# GameBoard.net
KiCad netlist of a schematic drawn in Altium Designer
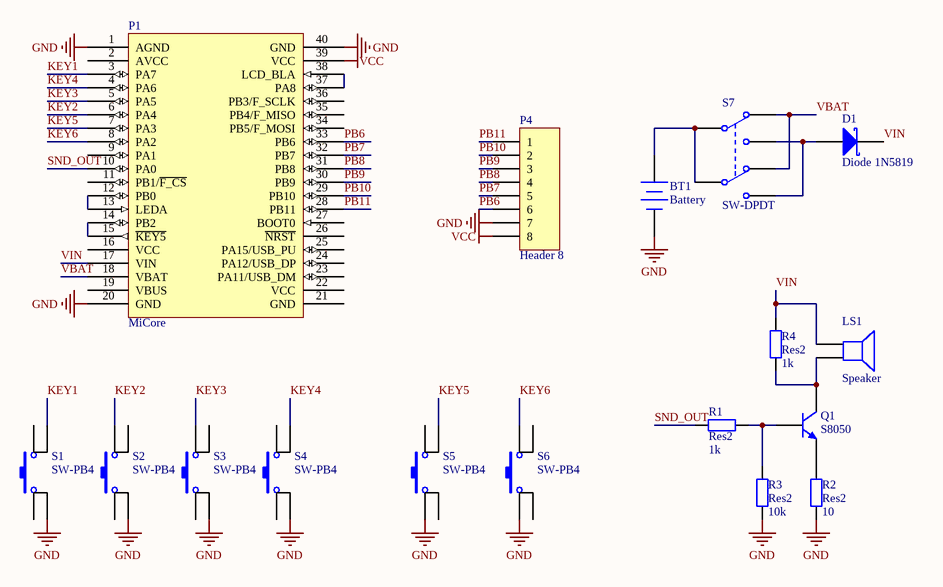
[diagram p0: GameBoard.SchDoc]

(export (version "E")
  (design (tool "Eeschema 10.0.6"))
  (components
    (comp (ref "BT1")
      (value "Battery")
      (footprint "BAT-2")
      (description "Multicell Battery")
      (fields (field (name "PUBLISHER") "Altium Limited"))
      (libsource (lib "Miscellaneous Devices") (part "Battery"))
    )
    (comp (ref "D1")
      (value "Diode 1N5819")
      (footprint "DO-204AL")
      (description "Schottky Rectifier")
      (fields (field (name "PUBLISHER") "Altium Limited"))
      (libsource (lib "Miscellaneous Devices") (part "Diode 11DQ03"))
    )
    (comp (ref "LS1")
      (value "Speaker")
      (footprint "PIN2")
      (description "Loudspeaker")
      (fields (field (name "PUBLISHER") "Altium Limited"))
      (libsource (lib "Miscellaneous Devices") (part "Speaker"))
    )
    (comp (ref "P1") (value "MiCore") (description "MiCore核心板") (libsource (lib "MiCore") (part "MiCore")))
    (comp (ref "P4")
      (value "Header 8")
      (footprint "HDR1X8")
      (description "Header, 8-Pin")
      (fields (field (name "PUBLISHER") "Altium Limited"))
      (libsource (lib "Miscellaneous Connectors") (part "Header 8"))
    )
    (comp (ref "Q1")
      (value "S8050")
      (footprint "TO-92")
      (description "NPN Bipolar Transistor")
      (fields (field (name "PUBLISHER") "Altium Limited"))
      (libsource (lib "Schlib1") (part "NPN"))
    )
    (comp (ref "R1")
      (value "Res2")
      (footprint "AXIAL-0.4")
      (description "Resistor")
      (fields (field (name "ALTIUM_VALUE") "1k") (field (name "PUBLISHER") "Altium Limited"))
      (libsource (lib "") (part "Res2_1"))
    )
    (comp (ref "R2")
      (value "Res2")
      (footprint "AXIAL-0.4")
      (description "Resistor")
      (fields (field (name "ALTIUM_VALUE") "10") (field (name "PUBLISHER") "Altium Limited"))
      (libsource (lib "Miscellaneous Devices") (part "Res2"))
    )
    (comp (ref "R3")
      (value "Res2")
      (footprint "AXIAL-0.4")
      (description "Resistor")
      (fields (field (name "ALTIUM_VALUE") "10k") (field (name "PUBLISHER") "Altium Limited"))
      (libsource (lib "Miscellaneous Devices") (part "Res2"))
    )
    (comp (ref "R4")
      (value "Res2")
      (footprint "AXIAL-0.4")
      (description "Resistor")
      (fields (field (name "ALTIUM_VALUE") "1k") (field (name "PUBLISHER") "Altium Limited"))
      (libsource (lib "Miscellaneous Devices") (part "Res2"))
    )
    (comp (ref "S1")
      (value "SW-PB4")
      (footprint "SW-PB-4P")
      (description "普通4脚按键")
      (libsource (lib "Schlib1") (part "SW-PB4"))
    )
    (comp (ref "S2")
      (value "SW-PB4")
      (footprint "SW-PB-4P")
      (description "普通4脚按键")
      (libsource (lib "Schlib1") (part "SW-PB4"))
    )
    (comp (ref "S3")
      (value "SW-PB4")
      (footprint "SW-PB-4P")
      (description "普通4脚按键")
      (libsource (lib "Schlib1") (part "SW-PB4"))
    )
    (comp (ref "S4")
      (value "SW-PB4")
      (footprint "SW-PB-4P")
      (description "普通4脚按键")
      (libsource (lib "Schlib1") (part "SW-PB4"))
    )
    (comp (ref "S5")
      (value "SW-PB4")
      (footprint "SW-PB-4P")
      (description "普通4脚按键")
      (libsource (lib "Schlib1") (part "SW-PB4"))
    )
    (comp (ref "S6")
      (value "SW-PB4")
      (footprint "SW-PB-4P")
      (description "普通4脚按键")
      (libsource (lib "Schlib1") (part "SW-PB4"))
    )
    (comp (ref "S7")
      (value "SW-DPDT")
      (footprint "DPDT-6P")
      (description "双刀双掷开关")
      (fields (field (name "PUBLISHER") "Altium Limited"))
      (libsource (lib "Schlib1") (part "SW-DPDT"))
    )
  )
  (nets
    (net (code "1") (name "/KEY1") (class "Default")
      (node (ref "P1") (pin "3") (pinfunction "PA7_3") (pintype "bidirectional"))
      (node (ref "S1") (pin "3") (pinfunction "3_3") (pintype "passive"))
    )
    (net (code "2") (name "/KEY2") (class "Default")
      (node (ref "P1") (pin "6") (pinfunction "PA4_6") (pintype "bidirectional"))
      (node (ref "S2") (pin "2") (pinfunction "2_2") (pintype "passive"))
    )
    (net (code "3") (name "/KEY3") (class "Default")
      (node (ref "P1") (pin "5") (pinfunction "PA5_5") (pintype "bidirectional"))
      (node (ref "S3") (pin "2") (pinfunction "2_2") (pintype "passive"))
    )
    (net (code "4") (name "/KEY4") (class "Default")
      (node (ref "P1") (pin "4") (pinfunction "PA6_4") (pintype "bidirectional"))
      (node (ref "S4") (pin "3") (pinfunction "3_3") (pintype "passive"))
    )
    (net (code "5") (name "/KEY5") (class "Default")
      (node (ref "P1") (pin "7") (pinfunction "PA3_7") (pintype "bidirectional"))
      (node (ref "S5") (pin "3") (pinfunction "3_3") (pintype "passive"))
    )
    (net (code "6") (name "/KEY6") (class "Default")
      (node (ref "P1") (pin "8") (pinfunction "PA2_8") (pintype "bidirectional"))
      (node (ref "S6") (pin "2") (pinfunction "2_2") (pintype "passive"))
    )
    (net (code "7") (name "/PB6") (class "Default")
      (node (ref "P1") (pin "33") (pinfunction "PB6_33") (pintype "bidirectional"))
      (node (ref "P4") (pin "6") (pinfunction "6_6") (pintype "passive"))
    )
    (net (code "8") (name "/PB7") (class "Default")
      (node (ref "P1") (pin "32") (pinfunction "PB7_32") (pintype "bidirectional"))
      (node (ref "P4") (pin "5") (pinfunction "5_5") (pintype "passive"))
    )
    (net (code "9") (name "/PB8") (class "Default")
      (node (ref "P1") (pin "31") (pinfunction "PB8_31") (pintype "bidirectional"))
      (node (ref "P4") (pin "4") (pinfunction "4_4") (pintype "passive"))
    )
    (net (code "10") (name "/PB9") (class "Default")
      (node (ref "P1") (pin "30") (pinfunction "PB9_30") (pintype "bidirectional"))
      (node (ref "P4") (pin "3") (pinfunction "3_3") (pintype "passive"))
    )
    (net (code "11") (name "/PB10") (class "Default")
      (node (ref "P1") (pin "29") (pinfunction "PB10_29") (pintype "bidirectional"))
      (node (ref "P4") (pin "2") (pinfunction "2_2") (pintype "passive"))
    )
    (net (code "12") (name "/PB11") (class "Default")
      (node (ref "P1") (pin "28") (pinfunction "PB11_28") (pintype "bidirectional"))
      (node (ref "P4") (pin "1") (pinfunction "1_1") (pintype "passive"))
    )
    (net (code "13") (name "/SND_OUT") (class "Default")
      (node (ref "P1") (pin "10") (pinfunction "PA0_10") (pintype "bidirectional"))
      (node (ref "R1") (pin "1") (pinfunction "1_1") (pintype "passive"))
    )
    (net (code "14") (name "/VBAT") (class "Default")
      (node (ref "P1") (pin "18") (pinfunction "VBAT_18") (pintype "power_in"))
      (node (ref "S7") (pin "1") (pinfunction "NC1_1") (pintype "passive"))
      (node (ref "S7") (pin "6") (pinfunction "NC2_6") (pintype "passive"))
    )
    (net (code "15") (name "/VIN") (class "Default")
      (node (ref "D1") (pin "2") (pinfunction "K_2") (pintype "passive"))
      (node (ref "LS1") (pin "1") (pinfunction "1_1") (pintype "passive"))
      (node (ref "P1") (pin "17") (pinfunction "VIN_17") (pintype "power_in"))
      (node (ref "R4") (pin "2") (pinfunction "2_2") (pintype "passive"))
    )
    (net (code "16") (name "GND") (class "Default")
      (node (ref "BT1") (pin "2") (pinfunction "-_2") (pintype "passive"))
      (node (ref "P1") (pin "1") (pinfunction "AGND_1") (pintype "power_in"))
      (node (ref "P1") (pin "20") (pinfunction "GND_20") (pintype "power_in"))
      (node (ref "P1") (pin "40") (pinfunction "GND_40") (pintype "power_in"))
      (node (ref "P4") (pin "7") (pinfunction "7_7") (pintype "passive"))
      (node (ref "R2") (pin "1") (pinfunction "1_1") (pintype "passive"))
      (node (ref "R3") (pin "1") (pinfunction "1_1") (pintype "passive"))
      (node (ref "S1") (pin "4") (pinfunction "4_4") (pintype "passive"))
      (node (ref "S2") (pin "4") (pinfunction "4_4") (pintype "passive"))
      (node (ref "S3") (pin "4") (pinfunction "4_4") (pintype "passive"))
      (node (ref "S4") (pin "4") (pinfunction "4_4") (pintype "passive"))
      (node (ref "S5") (pin "1") (pinfunction "1_1") (pintype "passive"))
      (node (ref "S6") (pin "1") (pinfunction "1_1") (pintype "passive"))
    )
    (net (code "17") (name "Net-(BT1-+)") (class "Default")
      (node (ref "BT1") (pin "1") (pinfunction "+_1") (pintype "passive"))
      (node (ref "S7") (pin "2") (pinfunction "COMMON1_2") (pintype "passive"))
      (node (ref "S7") (pin "5") (pinfunction "COMMON2_5") (pintype "passive"))
    )
    (net (code "18") (name "Net-(D1-A)") (class "Default")
      (node (ref "D1") (pin "1") (pinfunction "A_1") (pintype "passive"))
      (node (ref "S7") (pin "3") (pinfunction "NO1_3") (pintype "passive"))
      (node (ref "S7") (pin "4") (pinfunction "NO2_4") (pintype "passive"))
    )
    (net (code "19") (name "Net-(P1-LCD_BLA)") (class "Default")
      (node (ref "P1") (pin "37") (pinfunction "PA8_37") (pintype "bidirectional"))
      (node (ref "P1") (pin "38") (pinfunction "LCD_BLA_38") (pintype "input"))
    )
    (net (code "20") (name "Net-(P1-LEDA)") (class "Default")
      (node (ref "P1") (pin "12") (pinfunction "PB0_12") (pintype "bidirectional"))
      (node (ref "P1") (pin "13") (pinfunction "LEDA_13") (pintype "input"))
    )
    (net (code "21") (name "Net-(P1-PB2)") (class "Default")
      (node (ref "P1") (pin "14") (pinfunction "PB2_14") (pintype "bidirectional"))
      (node (ref "P1") (pin "15") (pinfunction "~{KEY5}_15") (pintype "output"))
    )
    (net (code "22") (name "Net-(Q1-B)") (class "Default")
      (node (ref "Q1") (pin "2") (pinfunction "B_2") (pintype "passive"))
      (node (ref "R1") (pin "2") (pinfunction "2_2") (pintype "passive"))
      (node (ref "R3") (pin "2") (pinfunction "2_2") (pintype "passive"))
    )
    (net (code "23") (name "Net-(Q1-C)") (class "Default")
      (node (ref "LS1") (pin "2") (pinfunction "2_2") (pintype "passive"))
      (node (ref "Q1") (pin "1") (pinfunction "C_1") (pintype "passive"))
      (node (ref "R4") (pin "1") (pinfunction "1_1") (pintype "passive"))
    )
    (net (code "24") (name "Net-(Q1-E)") (class "Default")
      (node (ref "Q1") (pin "3") (pinfunction "E_3") (pintype "passive"))
      (node (ref "R2") (pin "2") (pinfunction "2_2") (pintype "passive"))
    )
    (net (code "25") (name "VCC") (class "Default")
      (node (ref "P1") (pin "39") (pinfunction "VCC_39") (pintype "power_in"))
      (node (ref "P4") (pin "8") (pinfunction "8_8") (pintype "passive"))
    )
    (net (code "26") (name "unconnected-(P1-AVCC-Pad2)") (class "Default")
      (node (ref "P1") (pin "2") (pinfunction "AVCC_2") (pintype "power_in"))
    )
    (net (code "27") (name "unconnected-(P1-BOOT0-Pad27)") (class "Default")
      (node (ref "P1") (pin "27") (pinfunction "BOOT0_27") (pintype "input"))
    )
    (net (code "28") (name "unconnected-(P1-GND-Pad21)") (class "Default")
      (node (ref "P1") (pin "21") (pinfunction "GND_21") (pintype "power_in"))
    )
    (net (code "29") (name "unconnected-(P1-PA1-Pad9)") (class "Default")
      (node (ref "P1") (pin "9") (pinfunction "PA1_9") (pintype "bidirectional"))
    )
    (net (code "30") (name "unconnected-(P1-PA11{slash}USB_DM-Pad23)") (class "Default")
      (node (ref "P1") (pin "23") (pinfunction "PA11/USB_DM_23") (pintype "bidirectional"))
    )
    (net (code "31") (name "unconnected-(P1-PA12{slash}USB_DP-Pad24)") (class "Default")
      (node (ref "P1") (pin "24") (pinfunction "PA12/USB_DP_24") (pintype "bidirectional"))
    )
    (net (code "32") (name "unconnected-(P1-PA15{slash}USB_PU-Pad25)") (class "Default")
      (node (ref "P1") (pin "25") (pinfunction "PA15/USB_PU_25") (pintype "bidirectional"))
    )
    (net (code "33") (name "unconnected-(P1-PB1{slash}~{F_CS}-Pad11)") (class "Default")
      (node (ref "P1") (pin "11") (pinfunction "PB1/~{F_CS}_11") (pintype "bidirectional"))
    )
    (net (code "34") (name "unconnected-(P1-PB3{slash}F_SCLK-Pad36)") (class "Default")
      (node (ref "P1") (pin "36") (pinfunction "PB3/F_SCLK_36") (pintype "bidirectional"))
    )
    (net (code "35") (name "unconnected-(P1-PB4{slash}F_MISO-Pad35)") (class "Default")
      (node (ref "P1") (pin "35") (pinfunction "PB4/F_MISO_35") (pintype "bidirectional"))
    )
    (net (code "36") (name "unconnected-(P1-PB5{slash}F_MOSI-Pad34)") (class "Default")
      (node (ref "P1") (pin "34") (pinfunction "PB5/F_MOSI_34") (pintype "bidirectional"))
    )
    (net (code "37") (name "unconnected-(P1-VBUS-Pad19)") (class "Default")
      (node (ref "P1") (pin "19") (pinfunction "VBUS_19") (pintype "power_in"))
    )
    (net (code "38") (name "unconnected-(P1-VCC-Pad16)") (class "Default")
      (node (ref "P1") (pin "16") (pinfunction "VCC_16") (pintype "power_in"))
    )
    (net (code "39") (name "unconnected-(P1-VCC-Pad22)") (class "Default")
      (node (ref "P1") (pin "22") (pinfunction "VCC_22") (pintype "power_in"))
    )
    (net (code "40") (name "unconnected-(P1-~{NRST}-Pad26)") (class "Default")
      (node (ref "P1") (pin "26") (pinfunction "~{NRST}_26") (pintype "open_collector"))
    )
    (net (code "41") (name "unconnected-(S1-Pad1)") (class "Default")
      (node (ref "S1") (pin "1") (pinfunction "1_1") (pintype "passive"))
    )
    (net (code "42") (name "unconnected-(S1-Pad2)") (class "Default")
      (node (ref "S1") (pin "2") (pinfunction "2_2") (pintype "passive"))
    )
    (net (code "43") (name "unconnected-(S2-Pad1)") (class "Default")
      (node (ref "S2") (pin "1") (pinfunction "1_1") (pintype "passive"))
    )
    (net (code "44") (name "unconnected-(S2-Pad3)") (class "Default")
      (node (ref "S2") (pin "3") (pinfunction "3_3") (pintype "passive"))
    )
    (net (code "45") (name "unconnected-(S3-Pad1)") (class "Default")
      (node (ref "S3") (pin "1") (pinfunction "1_1") (pintype "passive"))
    )
    (net (code "46") (name "unconnected-(S3-Pad3)") (class "Default")
      (node (ref "S3") (pin "3") (pinfunction "3_3") (pintype "passive"))
    )
    (net (code "47") (name "unconnected-(S4-Pad1)") (class "Default")
      (node (ref "S4") (pin "1") (pinfunction "1_1") (pintype "passive"))
    )
    (net (code "48") (name "unconnected-(S4-Pad2)") (class "Default")
      (node (ref "S4") (pin "2") (pinfunction "2_2") (pintype "passive"))
    )
    (net (code "49") (name "unconnected-(S5-Pad2)") (class "Default")
      (node (ref "S5") (pin "2") (pinfunction "2_2") (pintype "passive"))
    )
    (net (code "50") (name "unconnected-(S5-Pad4)") (class "Default")
      (node (ref "S5") (pin "4") (pinfunction "4_4") (pintype "passive"))
    )
    (net (code "51") (name "unconnected-(S6-Pad3)") (class "Default")
      (node (ref "S6") (pin "3") (pinfunction "3_3") (pintype "passive"))
    )
    (net (code "52") (name "unconnected-(S6-Pad4)") (class "Default")
      (node (ref "S6") (pin "4") (pinfunction "4_4") (pintype "passive"))
    )
  )
)
